# LED_Dice.net
KiCad netlist of a schematic drawn in Altium Designer
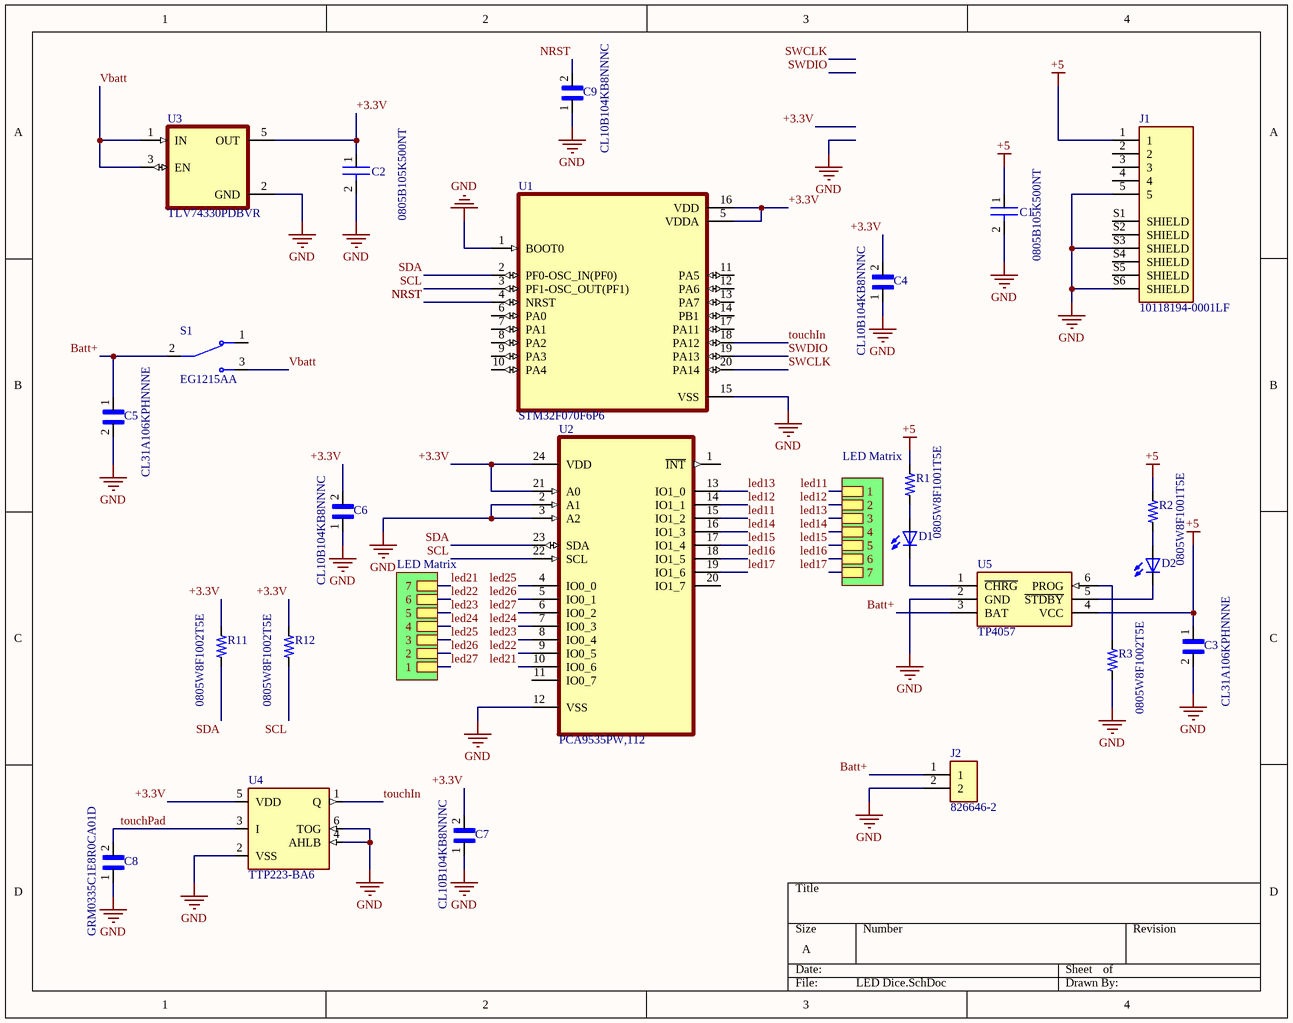
[diagram p0: LED Dice.SchDoc]

(export (version "E")
  (design (tool "Eeschema 10.0.6"))
  (components
    (comp (ref "C1")
      (value "0805B105K500NT")
      (footprint "CAPC2012X135N")
      (description "50V 1uF X7R ±10% 0805 Multilayer Ceramic Capacitors MLCC - SMD/SMT ROHS")
      (libsource (lib "Cap 0805 MLCC") (part "0805B105K500NT"))
    )
    (comp (ref "C2")
      (value "0805B105K500NT")
      (footprint "CAPC2012X135N")
      (description "50V 1uF X7R ±10% 0805 Multilayer Ceramic Capacitors MLCC - SMD/SMT ROHS")
      (libsource (lib "Cap 0805 MLCC") (part "0805B105K500NT"))
    )
    (comp (ref "C3")
      (value "CL31A106KPHNNNE")
      (footprint "CAPC3216X180N")
      (description "Cap Ceramic 10uF 10VDC X5R 10% SMD 1206 Embossed T/R")
      (libsource (lib "CL31A106KPHNNNE") (part "CL31A106KPHNNNE"))
    )
    (comp (ref "C4")
      (value "CL10B104KB8NNNC")
      (footprint "CAPC1608X90N")
      (description "0.1ÂµF Â±10% 50V Ceramic Capacitor X7R 0603 _1608 Metric_")
      (fields (field (name "MF") "Samsung Electro-Mechanics"))
      (libsource (lib "Cap 0603 MLCC") (part "CL10B104KB8NNNC"))
    )
    (comp (ref "C5")
      (value "CL31A106KPHNNNE")
      (footprint "CAPC3216X180N")
      (description "Cap Ceramic 10uF 10VDC X5R 10% SMD 1206 Embossed T/R")
      (libsource (lib "CL31A106KPHNNNE") (part "CL31A106KPHNNNE"))
    )
    (comp (ref "C6")
      (value "CL10B104KB8NNNC")
      (footprint "CAPC1608X90N")
      (description "0.1ÂµF Â±10% 50V Ceramic Capacitor X7R 0603 _1608 Metric_")
      (fields (field (name "MF") "Samsung Electro-Mechanics"))
      (libsource (lib "Cap 0603 MLCC") (part "CL10B104KB8NNNC"))
    )
    (comp (ref "C7")
      (value "CL10B104KB8NNNC")
      (footprint "CAPC1608X90N")
      (description "0.1ÂµF Â±10% 50V Ceramic Capacitor X7R 0603 _1608 Metric_")
      (fields (field (name "MF") "Samsung Electro-Mechanics"))
      (libsource (lib "Cap 0603 MLCC") (part "CL10B104KB8NNNC"))
    )
    (comp (ref "C8")
      (value "GRM0335C1E8R0CA01D")
      (footprint "CAPC1608X90N")
      (description "SMD Capacitor C0G(EIA) with Capacitance: 8.0pF Tol. 0.25pF. Rated Voltage: 25Vdc")
      (libsource (lib "Cap 0603 MLCC") (part "GRM0335C1E8R0CA01D"))
    )
    (comp (ref "C9")
      (value "CL10B104KB8NNNC")
      (footprint "CAPC1608X90N")
      (description "0.1ÂµF Â±10% 50V Ceramic Capacitor X7R 0603 _1608 Metric_")
      (fields (field (name "MF") "Samsung Electro-Mechanics"))
      (libsource (lib "Cap 0603 MLCC") (part "CL10B104KB8NNNC"))
    )
    (comp (ref "D1")
      (value "LTST-C171KRKT")
      (footprint "DIOC200X125X110")
      (description "Red LED  0805 _2012 Indication 631nm - Discrete 2V 0805 _2012 Metric_")
      (fields (field (name "MF") "Lite-On Inc."))
      (libsource (lib "LTST-C171KRKT") (part "LTST-C171KRKT"))
    )
    (comp (ref "D2")
      (value "LTST-C171KRKT")
      (footprint "DIOC200X125X110")
      (description "Red LED  0805 _2012 Indication 631nm - Discrete 2V 0805 _2012 Metric_")
      (fields (field (name "MF") "Lite-On Inc."))
      (libsource (lib "LTST-C171KRKT") (part "LTST-C171KRKT"))
    )
    (comp (ref "J1")
      (value "10118194-0001LF")
      (footprint "AMPHENOL_10118194-0001LF")
      (description "Micro USB, Input Output Connectors, B TYPE RECEPTACLE with flange")
      (fields (field (name "MF") "Amphenol ICC"))
      (libsource (lib "10118194-0001LF") (part "10118194-0001LF"))
    )
    (comp (ref "J2")
      (value "826646-2")
      (footprint "TE_826646-2")
      (description "Conn Unshrouded Header HDR 2 POS 2.54mm Solder ST Thru-Hole")
      (fields (field (name "MF") "TE Connectivity"))
      (libsource (lib "826646-2") (part "826646-2"))
    )
    (comp (ref "R1")
      (value "0805W8F1001T5E")
      (footprint "RESC2012X65N")
      (description "125mW Thick Film Resistors 150V ±100ppm/℃ ±1% 1kΩ 0805 Chip Resistor - Surface Mount ROHS")
      (libsource (lib "CRT0805-BW-1002ELF") (part "0805W8F1001T5E"))
    )
    (comp (ref "R2")
      (value "0805W8F1001T5E")
      (footprint "RESC2012X65N")
      (description "125mW Thick Film Resistors 150V ±100ppm/℃ ±1% 1kΩ 0805 Chip Resistor - Surface Mount ROHS")
      (libsource (lib "CRT0805-BW-1002ELF") (part "0805W8F1001T5E"))
    )
    (comp (ref "R3")
      (value "0805W8F1002T5E")
      (footprint "RESC2012X65N")
      (description "125mW Thick Film Resistors 150V ±100ppm/℃ ±1% 10kΩ 0805 Chip Resistor - Surface Mount ROHS")
      (libsource (lib "CRT0805-BW-1002ELF") (part "0805W8F1002T5E"))
    )
    (comp (ref "R11")
      (value "0805W8F1002T5E")
      (footprint "RESC2012X65N")
      (description "125mW Thick Film Resistors 150V ±100ppm/℃ ±1% 10kΩ 0805 Chip Resistor - Surface Mount ROHS")
      (libsource (lib "CRT0805-BW-1002ELF") (part "0805W8F1002T5E"))
    )
    (comp (ref "R12")
      (value "0805W8F1002T5E")
      (footprint "RESC2012X65N")
      (description "125mW Thick Film Resistors 150V ±100ppm/℃ ±1% 10kΩ 0805 Chip Resistor - Surface Mount ROHS")
      (libsource (lib "CRT0805-BW-1002ELF") (part "0805W8F1002T5E"))
    )
    (comp (ref "S1")
      (value "EG1215AA")
      (footprint "SW_EG1215AA")
      (description "Slide Switch SPDT Surface Mount, Right Angle")
      (fields (field (name "MF") "E-Switch"))
      (libsource (lib "EG1215AA") (part "EG1215AA"))
    )
    (comp (ref "U1")
      (value "STM32F070F6P6")
      (footprint "SOP65P640X120-20N")
      (description "ARMÂ® CortexÂ®-M0 STM32F0 Microcontroller IC 32-Bit Single-Core 48MHz 32KB (32K x 8) FLASH 20-TSSOP")
      (fields (field (name "MF") "STMicroelectronics"))
      (libsource (lib "STM32F070F6P6") (part "STM32F070F6P6"))
    )
    (comp (ref "U2")
      (value "PCA9535PW,112")
      (footprint "SOP65P640X110-24N")
      (description "16-bit I2C-bus and SMBus, low power I/O port with interrupt")
      (libsource (lib "PCA9535PW_112") (part "PCA9535PW,112"))
    )
    (comp (ref "U3")
      (value "TLV74330PDBVR")
      (footprint "SOT95P280X145-5N")
      (description "300-mA low-IQ low-dropout (LDO) voltage regulator with enable 5-SOT-23 -40 to 125")
      (fields (field (name "MF") "Texas Instruments"))
      (libsource (lib "TLV74330PDBVR") (part "TLV74330PDBVR"))
    )
    (comp (ref "U4")
      (value "TTP223-BA6")
      (footprint "SOT23-6")
      (fields (field (name "MF") "tontek"))
      (libsource (lib "TTP223-BA6") (part "TTP223-BA6"))
    )
    (comp (ref "U5")
      (value "TP4057")
      (footprint "SOT23-6")
      (fields (field (name "MF") "toppower"))
      (libsource (lib "TP4057") (part "TP4057"))
    )
  )
  (nets
    (net (code "1") (name "+5") (class "Default")
      (node (ref "C1") (pin "1") (pinfunction "A_1") (pintype "passive"))
      (node (ref "C3") (pin "1") (pinfunction "1_1") (pintype "passive"))
      (node (ref "J1") (pin "1") (pinfunction "1_1") (pintype "passive"))
      (node (ref "R1") (pin "2") (pinfunction "2_2") (pintype "passive"))
      (node (ref "R2") (pin "2") (pinfunction "2_2") (pintype "passive"))
      (node (ref "U5") (pin "4") (pinfunction "VCC_4") (pintype "power_in"))
    )
    (net (code "2") (name "/+3.3V") (class "Default")
      (node (ref "C2") (pin "1") (pinfunction "A_1") (pintype "passive"))
      (node (ref "C4") (pin "2") (pinfunction "2_2") (pintype "passive"))
      (node (ref "C6") (pin "2") (pinfunction "2_2") (pintype "passive"))
      (node (ref "C7") (pin "2") (pinfunction "2_2") (pintype "passive"))
      (node (ref "R11") (pin "2") (pinfunction "2_2") (pintype "passive"))
      (node (ref "R12") (pin "2") (pinfunction "2_2") (pintype "passive"))
      (node (ref "U1") (pin "16") (pinfunction "VDD_16") (pintype "power_in"))
      (node (ref "U1") (pin "5") (pinfunction "VDDA_5") (pintype "power_in"))
      (node (ref "U2") (pin "21") (pinfunction "A0_21") (pintype "input"))
      (node (ref "U2") (pin "24") (pinfunction "VDD_24") (pintype "power_in"))
      (node (ref "U3") (pin "5") (pinfunction "OUT_5") (pintype "power_in"))
      (node (ref "U4") (pin "5") (pinfunction "VDD_5") (pintype "power_in"))
    )
    (net (code "3") (name "/Batt+") (class "Default")
      (node (ref "C5") (pin "1") (pinfunction "1_1") (pintype "passive"))
      (node (ref "J2") (pin "1") (pinfunction "1_1") (pintype "passive"))
      (node (ref "S1") (pin "2") (pinfunction "2_2") (pintype "passive"))
      (node (ref "U5") (pin "3") (pinfunction "BAT_3") (pintype "power_in"))
    )
    (net (code "4") (name "/NRST") (class "Default")
      (node (ref "C9") (pin "2") (pinfunction "2_2") (pintype "passive"))
      (node (ref "U1") (pin "4") (pinfunction "NRST_4") (pintype "bidirectional"))
    )
    (net (code "5") (name "/SCL") (class "Default")
      (node (ref "R12") (pin "1") (pinfunction "1_1") (pintype "passive"))
      (node (ref "U1") (pin "3") (pinfunction "PF1-OSC_OUT(PF1)_3") (pintype "bidirectional"))
      (node (ref "U2") (pin "22") (pinfunction "SCL_22") (pintype "input"))
    )
    (net (code "6") (name "/SDA") (class "Default")
      (node (ref "R11") (pin "1") (pinfunction "1_1") (pintype "passive"))
      (node (ref "U1") (pin "2") (pinfunction "PF0-OSC_IN(PF0)_2") (pintype "bidirectional"))
      (node (ref "U2") (pin "23") (pinfunction "SDA_23") (pintype "bidirectional"))
    )
    (net (code "7") (name "/SWCLK") (class "Default")
      (node (ref "U1") (pin "20") (pinfunction "PA14_20") (pintype "bidirectional"))
    )
    (net (code "8") (name "/SWDIO") (class "Default")
      (node (ref "U1") (pin "19") (pinfunction "PA13_19") (pintype "bidirectional"))
    )
    (net (code "9") (name "/Vbatt") (class "Default")
      (node (ref "S1") (pin "3") (pinfunction "3_3") (pintype "passive"))
      (node (ref "U3") (pin "1") (pinfunction "IN_1") (pintype "input"))
      (node (ref "U3") (pin "3") (pinfunction "EN_3") (pintype "bidirectional"))
    )
    (net (code "10") (name "/led11") (class "Default")
      (node (ref "U2") (pin "15") (pinfunction "IO1_2_15") (pintype "passive"))
    )
    (net (code "11") (name "/led12") (class "Default")
      (node (ref "U2") (pin "14") (pinfunction "IO1_1_14") (pintype "passive"))
    )
    (net (code "12") (name "/led13") (class "Default")
      (node (ref "U2") (pin "13") (pinfunction "IO1_0_13") (pintype "passive"))
    )
    (net (code "13") (name "/led14") (class "Default")
      (node (ref "U2") (pin "16") (pinfunction "IO1_3_16") (pintype "passive"))
    )
    (net (code "14") (name "/led15") (class "Default")
      (node (ref "U2") (pin "17") (pinfunction "IO1_4_17") (pintype "passive"))
    )
    (net (code "15") (name "/led16") (class "Default")
      (node (ref "U2") (pin "18") (pinfunction "IO1_5_18") (pintype "passive"))
    )
    (net (code "16") (name "/led17") (class "Default")
      (node (ref "U2") (pin "19") (pinfunction "IO1_6_19") (pintype "passive"))
    )
    (net (code "17") (name "/led21") (class "Default")
      (node (ref "U2") (pin "10") (pinfunction "IO0_6_10") (pintype "passive"))
    )
    (net (code "18") (name "/led22") (class "Default")
      (node (ref "U2") (pin "9") (pinfunction "IO0_5_9") (pintype "passive"))
    )
    (net (code "19") (name "/led23") (class "Default")
      (node (ref "U2") (pin "8") (pinfunction "IO0_4_8") (pintype "passive"))
    )
    (net (code "20") (name "/led24") (class "Default")
      (node (ref "U2") (pin "7") (pinfunction "IO0_3_7") (pintype "passive"))
    )
    (net (code "21") (name "/led25") (class "Default")
      (node (ref "U2") (pin "4") (pinfunction "IO0_0_4") (pintype "passive"))
    )
    (net (code "22") (name "/led26") (class "Default")
      (node (ref "U2") (pin "5") (pinfunction "IO0_1_5") (pintype "passive"))
    )
    (net (code "23") (name "/led27") (class "Default")
      (node (ref "U2") (pin "6") (pinfunction "IO0_2_6") (pintype "passive"))
    )
    (net (code "24") (name "/touchIn") (class "Default")
      (node (ref "U1") (pin "18") (pinfunction "PA12_18") (pintype "bidirectional"))
      (node (ref "U4") (pin "1") (pinfunction "Q_1") (pintype "output"))
    )
    (net (code "25") (name "/touchPad") (class "Default")
      (node (ref "C8") (pin "2") (pinfunction "2_2") (pintype "passive"))
      (node (ref "U4") (pin "3") (pinfunction "I_3") (pintype "bidirectional"))
    )
    (net (code "26") (name "GND") (class "Default")
      (node (ref "C1") (pin "2") (pinfunction "C_2") (pintype "passive"))
      (node (ref "C2") (pin "2") (pinfunction "C_2") (pintype "passive"))
      (node (ref "C3") (pin "2") (pinfunction "2_2") (pintype "passive"))
      (node (ref "C4") (pin "1") (pinfunction "1_1") (pintype "passive"))
      (node (ref "C5") (pin "2") (pinfunction "2_2") (pintype "passive"))
      (node (ref "C6") (pin "1") (pinfunction "1_1") (pintype "passive"))
      (node (ref "C7") (pin "1") (pinfunction "1_1") (pintype "passive"))
      (node (ref "C8") (pin "1") (pinfunction "1_1") (pintype "passive"))
      (node (ref "C9") (pin "1") (pinfunction "1_1") (pintype "passive"))
      (node (ref "J1") (pin "5") (pinfunction "5_5") (pintype "passive"))
      (node (ref "J1") (pin "S3") (pinfunction "SHIELD_S3") (pintype "passive"))
      (node (ref "J1") (pin "S6") (pinfunction "SHIELD_S6") (pintype "passive"))
      (node (ref "J2") (pin "2") (pinfunction "2_2") (pintype "passive"))
      (node (ref "R3") (pin "1") (pinfunction "1_1") (pintype "passive"))
      (node (ref "U1") (pin "1") (pinfunction "BOOT0_1") (pintype "input"))
      (node (ref "U1") (pin "15") (pinfunction "VSS_15") (pintype "power_in"))
      (node (ref "U2") (pin "12") (pinfunction "VSS_12") (pintype "passive"))
      (node (ref "U2") (pin "2") (pinfunction "A1_2") (pintype "input"))
      (node (ref "U2") (pin "3") (pinfunction "A2_3") (pintype "input"))
      (node (ref "U3") (pin "2") (pinfunction "GND_2") (pintype "power_in"))
      (node (ref "U4") (pin "2") (pinfunction "VSS_2") (pintype "power_in"))
      (node (ref "U4") (pin "4") (pinfunction "AHLB_4") (pintype "input"))
      (node (ref "U4") (pin "6") (pinfunction "TOG_6") (pintype "input"))
      (node (ref "U5") (pin "2") (pinfunction "GND_2") (pintype "power_in"))
    )
    (net (code "27") (name "Net-(D1-PadPOS)") (class "Default")
      (node (ref "D1") (pin "POS") (pinfunction "POS_POS") (pintype "passive"))
      (node (ref "R1") (pin "1") (pinfunction "1_1") (pintype "passive"))
    )
    (net (code "28") (name "Net-(D2-PadPOS)") (class "Default")
      (node (ref "D2") (pin "POS") (pinfunction "POS_POS") (pintype "passive"))
      (node (ref "R2") (pin "1") (pinfunction "1_1") (pintype "passive"))
    )
    (net (code "29") (name "Net-(U5-PROG)") (class "Default")
      (node (ref "R3") (pin "2") (pinfunction "2_2") (pintype "passive"))
      (node (ref "U5") (pin "6") (pinfunction "PROG_6") (pintype "input"))
    )
    (net (code "30") (name "Net-(U5-~{CHRG})") (class "Default")
      (node (ref "D1") (pin "NEG") (pinfunction "NEG_NEG") (pintype "passive"))
      (node (ref "U5") (pin "1") (pinfunction "~{CHRG}_1") (pintype "open_collector"))
    )
    (net (code "31") (name "Net-(U5-~{STDBY})") (class "Default")
      (node (ref "D2") (pin "NEG") (pinfunction "NEG_NEG") (pintype "passive"))
      (node (ref "U5") (pin "5") (pinfunction "~{STDBY}_5") (pintype "open_collector"))
    )
    (net (code "32") (name "unconnected-(J1-Pad2)") (class "Default")
      (node (ref "J1") (pin "2") (pinfunction "2_2") (pintype "passive"))
    )
    (net (code "33") (name "unconnected-(J1-Pad3)") (class "Default")
      (node (ref "J1") (pin "3") (pinfunction "3_3") (pintype "passive"))
    )
    (net (code "34") (name "unconnected-(J1-Pad4)") (class "Default")
      (node (ref "J1") (pin "4") (pinfunction "4_4") (pintype "passive"))
    )
    (net (code "35") (name "unconnected-(J1-SHIELD-PadS1)") (class "Default")
      (node (ref "J1") (pin "S1") (pinfunction "SHIELD_S1") (pintype "passive"))
    )
    (net (code "36") (name "unconnected-(J1-SHIELD-PadS2)") (class "Default")
      (node (ref "J1") (pin "S2") (pinfunction "SHIELD_S2") (pintype "passive"))
    )
    (net (code "37") (name "unconnected-(J1-SHIELD-PadS4)") (class "Default")
      (node (ref "J1") (pin "S4") (pinfunction "SHIELD_S4") (pintype "passive"))
    )
    (net (code "38") (name "unconnected-(J1-SHIELD-PadS5)") (class "Default")
      (node (ref "J1") (pin "S5") (pinfunction "SHIELD_S5") (pintype "passive"))
    )
    (net (code "39") (name "unconnected-(S1-Pad1)") (class "Default")
      (node (ref "S1") (pin "1") (pinfunction "1_1") (pintype "passive"))
    )
    (net (code "40") (name "unconnected-(U1-PA0-Pad6)") (class "Default")
      (node (ref "U1") (pin "6") (pinfunction "PA0_6") (pintype "bidirectional"))
    )
    (net (code "41") (name "unconnected-(U1-PA1-Pad7)") (class "Default")
      (node (ref "U1") (pin "7") (pinfunction "PA1_7") (pintype "bidirectional"))
    )
    (net (code "42") (name "unconnected-(U1-PA2-Pad8)") (class "Default")
      (node (ref "U1") (pin "8") (pinfunction "PA2_8") (pintype "bidirectional"))
    )
    (net (code "43") (name "unconnected-(U1-PA3-Pad9)") (class "Default")
      (node (ref "U1") (pin "9") (pinfunction "PA3_9") (pintype "bidirectional"))
    )
    (net (code "44") (name "unconnected-(U1-PA4-Pad10)") (class "Default")
      (node (ref "U1") (pin "10") (pinfunction "PA4_10") (pintype "bidirectional"))
    )
    (net (code "45") (name "unconnected-(U1-PA5-Pad11)") (class "Default")
      (node (ref "U1") (pin "11") (pinfunction "PA5_11") (pintype "bidirectional"))
    )
    (net (code "46") (name "unconnected-(U1-PA6-Pad12)") (class "Default")
      (node (ref "U1") (pin "12") (pinfunction "PA6_12") (pintype "bidirectional"))
    )
    (net (code "47") (name "unconnected-(U1-PA7-Pad13)") (class "Default")
      (node (ref "U1") (pin "13") (pinfunction "PA7_13") (pintype "bidirectional"))
    )
    (net (code "48") (name "unconnected-(U1-PA11-Pad17)") (class "Default")
      (node (ref "U1") (pin "17") (pinfunction "PA11_17") (pintype "bidirectional"))
    )
    (net (code "49") (name "unconnected-(U1-PB1-Pad14)") (class "Default")
      (node (ref "U1") (pin "14") (pinfunction "PB1_14") (pintype "bidirectional"))
    )
    (net (code "50") (name "unconnected-(U2-IO0_7-Pad11)") (class "Default")
      (node (ref "U2") (pin "11") (pinfunction "IO0_7_11") (pintype "passive"))
    )
    (net (code "51") (name "unconnected-(U2-IO1_7-Pad20)") (class "Default")
      (node (ref "U2") (pin "20") (pinfunction "IO1_7_20") (pintype "passive"))
    )
    (net (code "52") (name "unconnected-(U2-~{INT}-Pad1)") (class "Default")
      (node (ref "U2") (pin "1") (pinfunction "~{INT}_1") (pintype "output"))
    )
  )
)
